# Dock.net
KiCad netlist of a schematic drawn in EAGLE
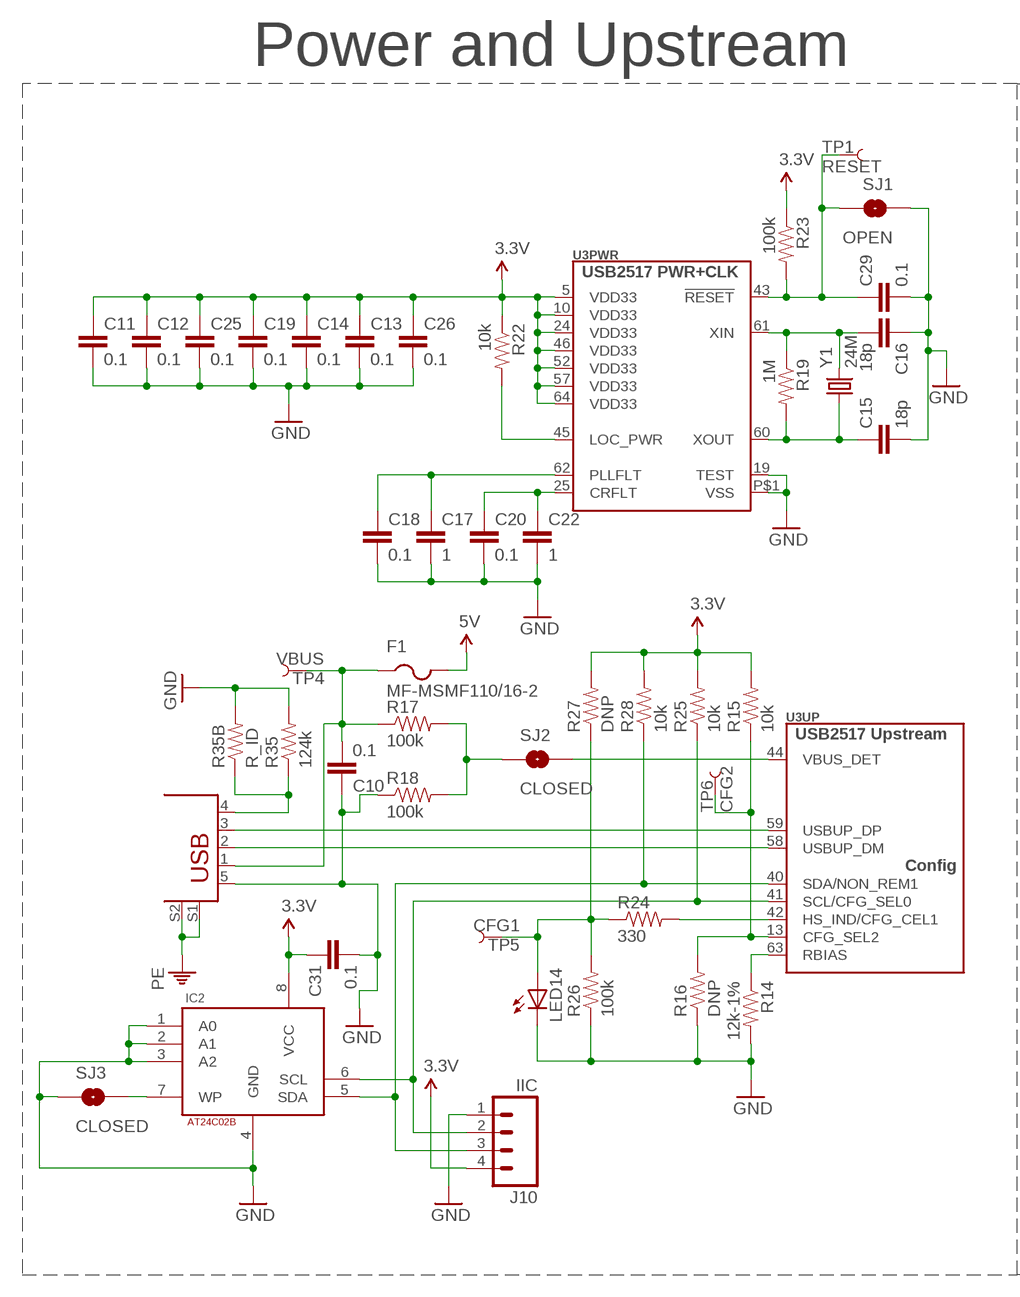
[diagram p0: schematic, sheet 1, part 1 of 2]
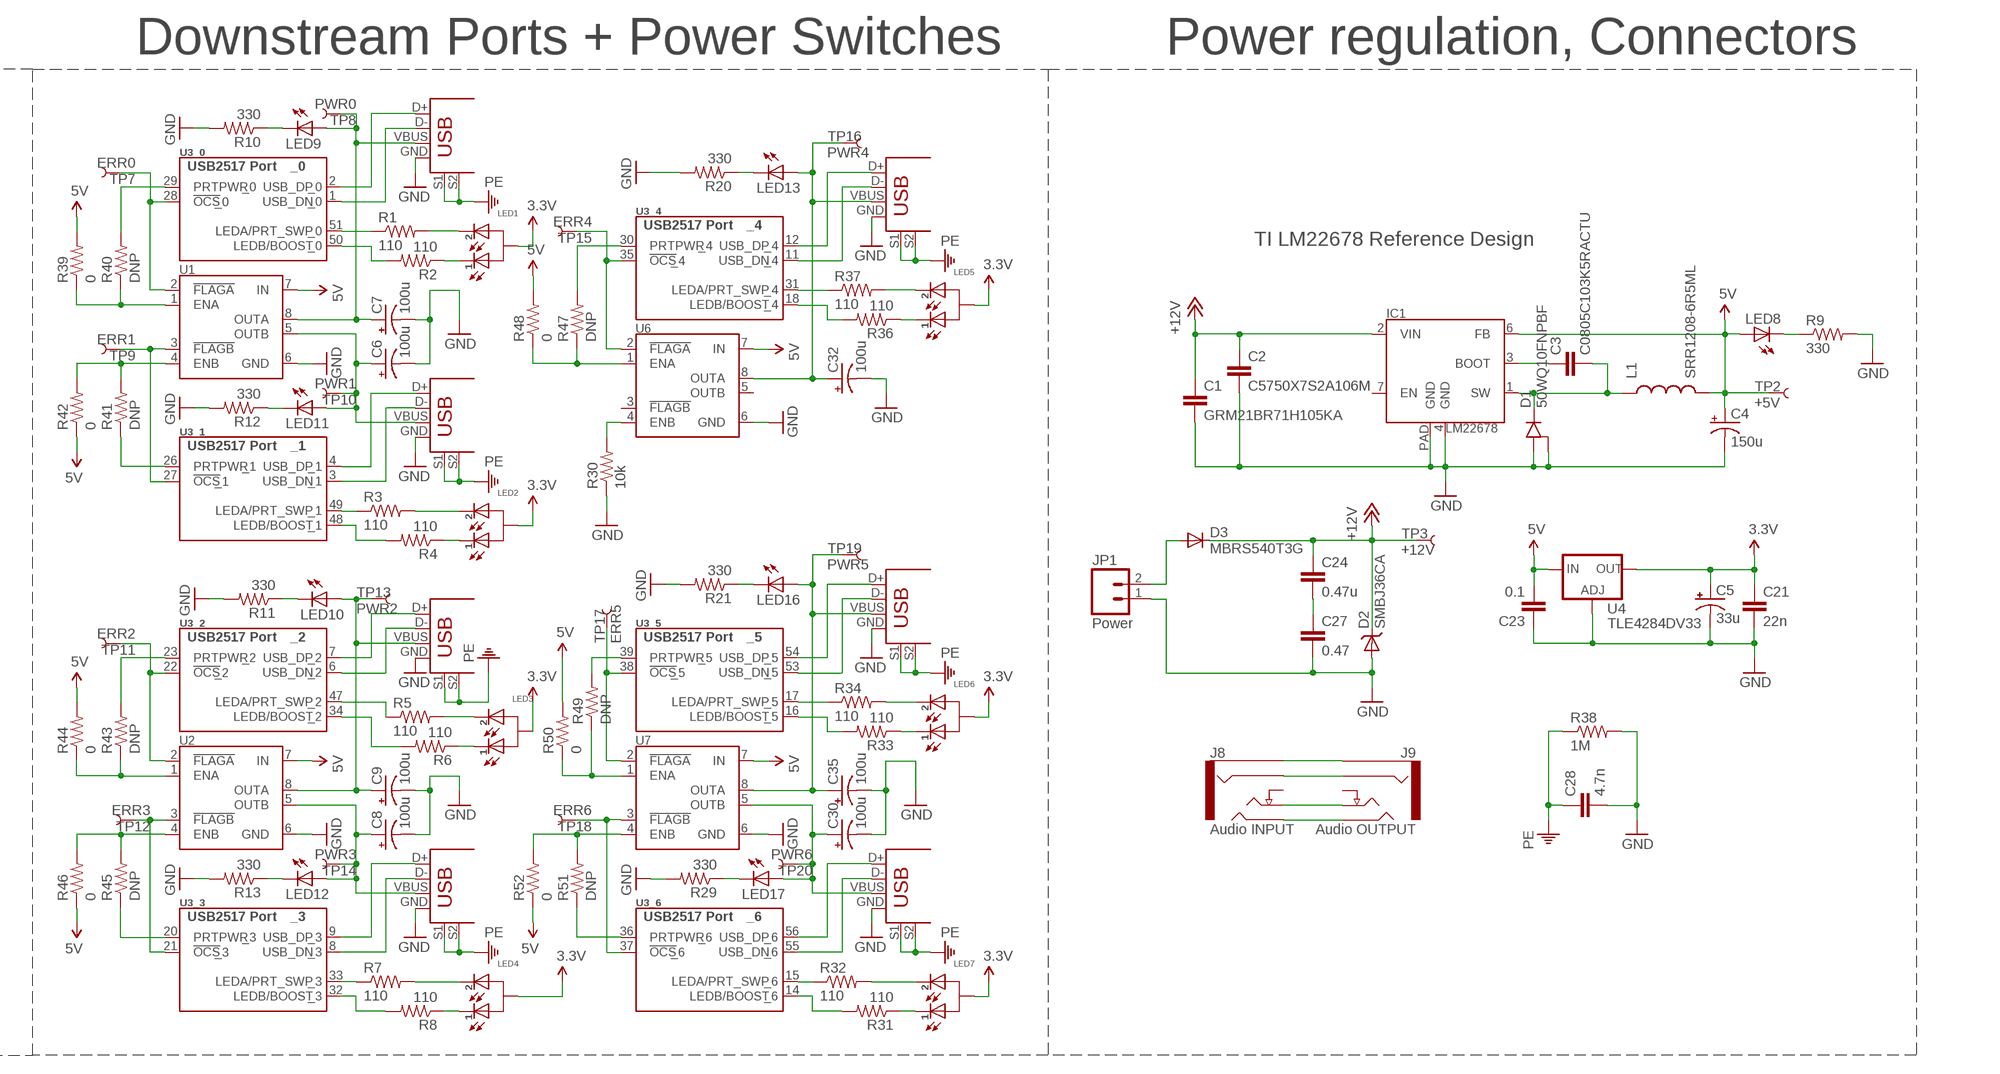
[diagram p1: schematic, sheet 1, part 2 of 2]

(export (version "E")
  (design (tool "Eeschema 10.0.6"))
  (components
    (comp (ref "C1")
      (value "GRM21BR71H105KA")
      (footprint "eagle-import:0805")
      (libsource (lib "eagle-import") (part "CAP0805"))
    )
    (comp (ref "C2")
      (value "C5750X7S2A106M")
      (footprint "eagle-import:2220")
      (libsource (lib "eagle-import") (part "CAP2220"))
    )
    (comp (ref "C3")
      (value "C0805C103K5RACTU")
      (footprint "eagle-import:0805")
      (libsource (lib "eagle-import") (part "CAP0805"))
    )
    (comp (ref "C4")
      (value "150u")
      (footprint "eagle-import:PANASONIC_D")
      (libsource (lib "eagle-import") (part "CAP_POLD"))
    )
    (comp (ref "C5")
      (value "33u")
      (footprint "eagle-import:PANASONIC_C")
      (libsource (lib "eagle-import") (part "CAP_POLC"))
    )
    (comp (ref "C6")
      (value "100u")
      (footprint "eagle-import:PANASONIC_D")
      (libsource (lib "eagle-import") (part "CAP_POLD"))
    )
    (comp (ref "C7")
      (value "100u")
      (footprint "eagle-import:PANASONIC_D")
      (libsource (lib "eagle-import") (part "CAP_POLD"))
    )
    (comp (ref "C8")
      (value "100u")
      (footprint "eagle-import:PANASONIC_D")
      (libsource (lib "eagle-import") (part "CAP_POLD"))
    )
    (comp (ref "C9")
      (value "100u")
      (footprint "eagle-import:PANASONIC_D")
      (libsource (lib "eagle-import") (part "CAP_POLD"))
    )
    (comp (ref "C10")
      (value "0.1")
      (footprint "eagle-import:0402-CAP")
      (libsource (lib "eagle-import") (part "CAP0402-CAP"))
    )
    (comp (ref "C11")
      (value "0.1")
      (footprint "eagle-import:0402-CAP")
      (libsource (lib "eagle-import") (part "CAP0402-CAP"))
    )
    (comp (ref "C12")
      (value "0.1")
      (footprint "eagle-import:0402-CAP")
      (libsource (lib "eagle-import") (part "CAP0402-CAP"))
    )
    (comp (ref "C13")
      (value "0.1")
      (footprint "eagle-import:0402-CAP")
      (libsource (lib "eagle-import") (part "CAP0402-CAP"))
    )
    (comp (ref "C14")
      (value "0.1")
      (footprint "eagle-import:0402-CAP")
      (libsource (lib "eagle-import") (part "CAP0402-CAP"))
    )
    (comp (ref "C15")
      (value "18p")
      (footprint "eagle-import:0402-CAP")
      (libsource (lib "eagle-import") (part "CAP0402-CAP"))
    )
    (comp (ref "C16")
      (value "18p")
      (footprint "eagle-import:0402-CAP")
      (libsource (lib "eagle-import") (part "CAP0402-CAP"))
    )
    (comp (ref "C17")
      (value "1")
      (footprint "eagle-import:0402-CAP")
      (libsource (lib "eagle-import") (part "CAP0402-CAP"))
    )
    (comp (ref "C18")
      (value "0.1")
      (footprint "eagle-import:0402-CAP")
      (libsource (lib "eagle-import") (part "CAP0402-CAP"))
    )
    (comp (ref "C19")
      (value "0.1")
      (footprint "eagle-import:0402-CAP")
      (libsource (lib "eagle-import") (part "CAP0402-CAP"))
    )
    (comp (ref "C20")
      (value "0.1")
      (footprint "eagle-import:0402-CAP")
      (libsource (lib "eagle-import") (part "CAP0402-CAP"))
    )
    (comp (ref "C21")
      (value "22n")
      (footprint "eagle-import:0402-CAP")
      (libsource (lib "eagle-import") (part "CAP0402-CAP"))
    )
    (comp (ref "C22")
      (value "1")
      (footprint "eagle-import:0402-CAP")
      (libsource (lib "eagle-import") (part "CAP0402-CAP"))
    )
    (comp (ref "C23")
      (value "0.1")
      (footprint "eagle-import:0402-CAP")
      (libsource (lib "eagle-import") (part "CAP0402-CAP"))
    )
    (comp (ref "C24")
      (value "0.47u")
      (footprint "eagle-import:0805")
      (libsource (lib "eagle-import") (part "CAP0805"))
    )
    (comp (ref "C25")
      (value "0.1")
      (footprint "eagle-import:0402-CAP")
      (libsource (lib "eagle-import") (part "CAP0402-CAP"))
    )
    (comp (ref "C26")
      (value "0.1")
      (footprint "eagle-import:0402-CAP")
      (libsource (lib "eagle-import") (part "CAP0402-CAP"))
    )
    (comp (ref "C27")
      (value "0.47")
      (footprint "eagle-import:0805")
      (libsource (lib "eagle-import") (part "CAP0805"))
    )
    (comp (ref "C28")
      (value "4.7n")
      (footprint "eagle-import:0805")
      (libsource (lib "eagle-import") (part "CAP0805"))
    )
    (comp (ref "C29")
      (value "0.1")
      (footprint "eagle-import:0402-CAP")
      (libsource (lib "eagle-import") (part "CAP0402-CAP"))
    )
    (comp (ref "C30")
      (value "100u")
      (footprint "eagle-import:PANASONIC_D")
      (libsource (lib "eagle-import") (part "CAP_POLD"))
    )
    (comp (ref "C31")
      (value "0.1")
      (footprint "eagle-import:0402-CAP")
      (libsource (lib "eagle-import") (part "CAP0402-CAP"))
    )
    (comp (ref "C32")
      (value "100u")
      (footprint "eagle-import:PANASONIC_D")
      (libsource (lib "eagle-import") (part "CAP_POLD"))
    )
    (comp (ref "C35")
      (value "100u")
      (footprint "eagle-import:PANASONIC_D")
      (libsource (lib "eagle-import") (part "CAP_POLD"))
    )
    (comp (ref "D1")
      (value "50WQ10FNPBF")
      (footprint "eagle-import:V-REG_DPACK")
      (libsource (lib "eagle-import") (part "DIODE_COMMON_CAT-DPAK"))
    )
    (comp (ref "D2")
      (value "SMBJ36CA")
      (footprint "eagle-import:SMB-DIODE")
      (libsource (lib "eagle-import") (part "DIODE-TVS-SMB"))
    )
    (comp (ref "D3")
      (value "MBRS540T3G")
      (footprint "eagle-import:SMC")
      (libsource (lib "eagle-import") (part "DIODESMC/DO-214AB"))
    )
    (comp (ref "F1")
      (value "MF-MSMF110/16-2")
      (footprint "eagle-import:1812")
      (libsource (lib "eagle-import") (part "PTCFUSE-1812"))
    )
    (comp (ref "IC1")
      (value "LM22678")
      (footprint "eagle-import:TO-263")
      (libsource (lib "eagle-import") (part "LM22678"))
    )
    (comp (ref "IC2")
      (value "ATMEL-AT24C02B-SS")
      (footprint "eagle-import:SOIC8")
      (libsource (lib "eagle-import") (part "ATMEL-AT24C02B-SS"))
    )
    (comp (ref "J0")
      (value "USB_MINIB_SHIELD-10118193")
      (footprint "eagle-import:10118193")
      (libsource (lib "eagle-import") (part "USB_MINIB_SHIELD-10118193"))
    )
    (comp (ref "J1")
      (value "USB-A-S-RA-VERT")
      (footprint "eagle-import:USB-A-TH-VERT")
      (libsource (lib "eagle-import") (part "USB-A-S-RA-VERT"))
    )
    (comp (ref "J2")
      (value "USB-A-S-RA-VERT")
      (footprint "eagle-import:USB-A-TH-VERT")
      (libsource (lib "eagle-import") (part "USB-A-S-RA-VERT"))
    )
    (comp (ref "J3")
      (value "USB-A-S-RA-VERT")
      (footprint "eagle-import:USB-A-TH-VERT")
      (libsource (lib "eagle-import") (part "USB-A-S-RA-VERT"))
    )
    (comp (ref "J4")
      (value "USB-A-S-RA-VERT")
      (footprint "eagle-import:USB-A-TH-VERT")
      (libsource (lib "eagle-import") (part "USB-A-S-RA-VERT"))
    )
    (comp (ref "J5")
      (value "USB-A-S-RA-VERT")
      (footprint "eagle-import:USB-A-TH-VERT")
      (libsource (lib "eagle-import") (part "USB-A-S-RA-VERT"))
    )
    (comp (ref "J6")
      (value "USB-A-S-RA-VERT")
      (footprint "eagle-import:USB-A-TH-VERT")
      (libsource (lib "eagle-import") (part "USB-A-S-RA-VERT"))
    )
    (comp (ref "J7")
      (value "USB-A-S-RA-VERT")
      (footprint "eagle-import:USB-A-TH-VERT")
      (libsource (lib "eagle-import") (part "USB-A-S-RA-VERT"))
    )
    (comp (ref "J8")
      (value "Audio INPUT")
      (footprint "eagle-import:SJ-4351X")
      (libsource (lib "eagle-import") (part "AUDIO-JACK-4PSWSJ-43515"))
    )
    (comp (ref "J9")
      (value "Audio OUTPUT")
      (footprint "eagle-import:SJ-4351X")
      (libsource (lib "eagle-import") (part "AUDIO-JACK-4PSWSJ-43515"))
    )
    (comp (ref "J10")
      (value "IIC")
      (footprint "eagle-import:1X04")
      (libsource (lib "eagle-import") (part "M04PTH"))
    )
    (comp (ref "JP1")
      (value "Power")
      (footprint "eagle-import:2-1445055-2")
      (libsource (lib "eagle-import") (part "M022-1445055-2"))
    )
    (comp (ref "L1")
      (value "SRR1208-6R5ML")
      (footprint "eagle-import:SRR1208")
      (libsource (lib "eagle-import") (part "INDUCTORSRR1208"))
    )
    (comp (ref "LED1")
      (value "LED_2X_COMMON_ANODE")
      (footprint "eagle-import:LED_DUAL_3MMX1MM")
      (libsource (lib "eagle-import") (part "LED_2X_COMMON_ANODE"))
    )
    (comp (ref "LED2")
      (value "LED_2X_COMMON_ANODE")
      (footprint "eagle-import:LED_DUAL_3MMX1MM")
      (libsource (lib "eagle-import") (part "LED_2X_COMMON_ANODE"))
    )
    (comp (ref "LED3")
      (value "LED_2X_COMMON_ANODE")
      (footprint "eagle-import:LED_DUAL_3MMX1MM")
      (libsource (lib "eagle-import") (part "LED_2X_COMMON_ANODE"))
    )
    (comp (ref "LED4")
      (value "LED_2X_COMMON_ANODE")
      (footprint "eagle-import:LED_DUAL_3MMX1MM")
      (libsource (lib "eagle-import") (part "LED_2X_COMMON_ANODE"))
    )
    (comp (ref "LED5")
      (value "LED_2X_COMMON_ANODE")
      (footprint "eagle-import:LED_DUAL_3MMX1MM")
      (libsource (lib "eagle-import") (part "LED_2X_COMMON_ANODE"))
    )
    (comp (ref "LED6")
      (value "LED_2X_COMMON_ANODE")
      (footprint "eagle-import:LED_DUAL_3MMX1MM")
      (libsource (lib "eagle-import") (part "LED_2X_COMMON_ANODE"))
    )
    (comp (ref "LED7")
      (value "LED_2X_COMMON_ANODE")
      (footprint "eagle-import:LED_DUAL_3MMX1MM")
      (libsource (lib "eagle-import") (part "LED_2X_COMMON_ANODE"))
    )
    (comp (ref "LED8")
      (value "LED0603")
      (footprint "eagle-import:LED-0603")
      (libsource (lib "eagle-import") (part "LED0603"))
    )
    (comp (ref "LED9")
      (value "LED0603")
      (footprint "eagle-import:LED-0603")
      (libsource (lib "eagle-import") (part "LED0603"))
    )
    (comp (ref "LED10")
      (value "LED0603")
      (footprint "eagle-import:LED-0603")
      (libsource (lib "eagle-import") (part "LED0603"))
    )
    (comp (ref "LED11")
      (value "LED0603")
      (footprint "eagle-import:LED-0603")
      (libsource (lib "eagle-import") (part "LED0603"))
    )
    (comp (ref "LED12")
      (value "LED0603")
      (footprint "eagle-import:LED-0603")
      (libsource (lib "eagle-import") (part "LED0603"))
    )
    (comp (ref "LED13")
      (value "LED0603")
      (footprint "eagle-import:LED-0603")
      (libsource (lib "eagle-import") (part "LED0603"))
    )
    (comp (ref "LED14")
      (value "LED0603")
      (footprint "eagle-import:LED-0603")
      (libsource (lib "eagle-import") (part "LED0603"))
    )
    (comp (ref "LED16")
      (value "LED0603")
      (footprint "eagle-import:LED-0603")
      (libsource (lib "eagle-import") (part "LED0603"))
    )
    (comp (ref "LED17")
      (value "LED0603")
      (footprint "eagle-import:LED-0603")
      (libsource (lib "eagle-import") (part "LED0603"))
    )
    (comp (ref "R1")
      (value "110")
      (footprint "eagle-import:0402-RES")
      (libsource (lib "eagle-import") (part "RESISTOR0402-RES"))
    )
    (comp (ref "R2")
      (value "110")
      (footprint "eagle-import:0402-RES")
      (libsource (lib "eagle-import") (part "RESISTOR0402-RES"))
    )
    (comp (ref "R3")
      (value "110")
      (footprint "eagle-import:0402-RES")
      (libsource (lib "eagle-import") (part "RESISTOR0402-RES"))
    )
    (comp (ref "R4")
      (value "110")
      (footprint "eagle-import:0402-RES")
      (libsource (lib "eagle-import") (part "RESISTOR0402-RES"))
    )
    (comp (ref "R5")
      (value "110")
      (footprint "eagle-import:0402-RES")
      (libsource (lib "eagle-import") (part "RESISTOR0402-RES"))
    )
    (comp (ref "R6")
      (value "110")
      (footprint "eagle-import:0402-RES")
      (libsource (lib "eagle-import") (part "RESISTOR0402-RES"))
    )
    (comp (ref "R7")
      (value "110")
      (footprint "eagle-import:0402-RES")
      (libsource (lib "eagle-import") (part "RESISTOR0402-RES"))
    )
    (comp (ref "R8")
      (value "110")
      (footprint "eagle-import:0402-RES")
      (libsource (lib "eagle-import") (part "RESISTOR0402-RES"))
    )
    (comp (ref "R9")
      (value "330")
      (footprint "eagle-import:0402-RES")
      (libsource (lib "eagle-import") (part "RESISTOR0402-RES"))
    )
    (comp (ref "R10")
      (value "330")
      (footprint "eagle-import:0402-RES")
      (libsource (lib "eagle-import") (part "RESISTOR0402-RES"))
    )
    (comp (ref "R11")
      (value "330")
      (footprint "eagle-import:0402-RES")
      (libsource (lib "eagle-import") (part "RESISTOR0402-RES"))
    )
    (comp (ref "R12")
      (value "330")
      (footprint "eagle-import:0402-RES")
      (libsource (lib "eagle-import") (part "RESISTOR0402-RES"))
    )
    (comp (ref "R13")
      (value "330")
      (footprint "eagle-import:0402-RES")
      (libsource (lib "eagle-import") (part "RESISTOR0402-RES"))
    )
    (comp (ref "R14")
      (value "12k-1%")
      (footprint "eagle-import:0402-RES")
      (libsource (lib "eagle-import") (part "RESISTOR0402-RES"))
    )
    (comp (ref "R15")
      (value "10k")
      (footprint "eagle-import:0402-RES")
      (libsource (lib "eagle-import") (part "RESISTOR0402-RES"))
    )
    (comp (ref "R16")
      (value "DNP")
      (footprint "eagle-import:0402-RES")
      (libsource (lib "eagle-import") (part "RESISTOR0402-RES"))
    )
    (comp (ref "R17")
      (value "100k")
      (footprint "eagle-import:0402-RES")
      (libsource (lib "eagle-import") (part "RESISTOR0402-RES"))
    )
    (comp (ref "R18")
      (value "100k")
      (footprint "eagle-import:0402-RES")
      (libsource (lib "eagle-import") (part "RESISTOR0402-RES"))
    )
    (comp (ref "R19")
      (value "1M")
      (footprint "eagle-import:0402-RES")
      (libsource (lib "eagle-import") (part "RESISTOR0402-RES"))
    )
    (comp (ref "R20")
      (value "330")
      (footprint "eagle-import:0402-RES")
      (libsource (lib "eagle-import") (part "RESISTOR0402-RES"))
    )
    (comp (ref "R21")
      (value "330")
      (footprint "eagle-import:0402-RES")
      (libsource (lib "eagle-import") (part "RESISTOR0402-RES"))
    )
    (comp (ref "R22")
      (value "10k")
      (footprint "eagle-import:0402-RES")
      (libsource (lib "eagle-import") (part "RESISTOR0402-RES"))
    )
    (comp (ref "R23")
      (value "100k")
      (footprint "eagle-import:0402-RES")
      (libsource (lib "eagle-import") (part "RESISTOR0402-RES"))
    )
    (comp (ref "R24")
      (value "330")
      (footprint "eagle-import:0402-RES")
      (libsource (lib "eagle-import") (part "RESISTOR0402-RES"))
    )
    (comp (ref "R25")
      (value "10k")
      (footprint "eagle-import:0402-RES")
      (libsource (lib "eagle-import") (part "RESISTOR0402-RES"))
    )
    (comp (ref "R26")
      (value "100k")
      (footprint "eagle-import:0402-RES")
      (libsource (lib "eagle-import") (part "RESISTOR0402-RES"))
    )
    (comp (ref "R27")
      (value "DNP")
      (footprint "eagle-import:0402-RES")
      (libsource (lib "eagle-import") (part "RESISTOR0402-RES"))
    )
    (comp (ref "R28")
      (value "10k")
      (footprint "eagle-import:0402-RES")
      (libsource (lib "eagle-import") (part "RESISTOR0402-RES"))
    )
    (comp (ref "R29")
      (value "330")
      (footprint "eagle-import:0402-RES")
      (libsource (lib "eagle-import") (part "RESISTOR0402-RES"))
    )
    (comp (ref "R30")
      (value "10k")
      (footprint "eagle-import:0402-RES")
      (libsource (lib "eagle-import") (part "RESISTOR0402-RES"))
    )
    (comp (ref "R31")
      (value "110")
      (footprint "eagle-import:0402-RES")
      (libsource (lib "eagle-import") (part "RESISTOR0402-RES"))
    )
    (comp (ref "R32")
      (value "110")
      (footprint "eagle-import:0402-RES")
      (libsource (lib "eagle-import") (part "RESISTOR0402-RES"))
    )
    (comp (ref "R33")
      (value "110")
      (footprint "eagle-import:0402-RES")
      (libsource (lib "eagle-import") (part "RESISTOR0402-RES"))
    )
    (comp (ref "R34")
      (value "110")
      (footprint "eagle-import:0402-RES")
      (libsource (lib "eagle-import") (part "RESISTOR0402-RES"))
    )
    (comp (ref "R35")
      (value "124k")
      (footprint "eagle-import:0402-RES")
      (libsource (lib "eagle-import") (part "RESISTOR0402-RES"))
    )
    (comp (ref "R35B")
      (value "R_ID")
      (footprint "eagle-import:AXIAL-0.4")
      (libsource (lib "eagle-import") (part "RESISTORPTH-1/4W"))
    )
    (comp (ref "R36")
      (value "110")
      (footprint "eagle-import:0402-RES")
      (libsource (lib "eagle-import") (part "RESISTOR0402-RES"))
    )
    (comp (ref "R37")
      (value "110")
      (footprint "eagle-import:0402-RES")
      (libsource (lib "eagle-import") (part "RESISTOR0402-RES"))
    )
    (comp (ref "R38")
      (value "1M")
      (footprint "eagle-import:0805")
      (libsource (lib "eagle-import") (part "RESISTOR0805-RES"))
    )
    (comp (ref "R39")
      (value "0")
      (footprint "eagle-import:0402-RES")
      (libsource (lib "eagle-import") (part "RESISTOR0402-RES"))
    )
    (comp (ref "R40")
      (value "DNP")
      (footprint "eagle-import:0402-RES")
      (libsource (lib "eagle-import") (part "RESISTOR0402-RES"))
    )
    (comp (ref "R41")
      (value "DNP")
      (footprint "eagle-import:0402-RES")
      (libsource (lib "eagle-import") (part "RESISTOR0402-RES"))
    )
    (comp (ref "R42")
      (value "0")
      (footprint "eagle-import:0402-RES")
      (libsource (lib "eagle-import") (part "RESISTOR0402-RES"))
    )
    (comp (ref "R43")
      (value "DNP")
      (footprint "eagle-import:0402-RES")
      (libsource (lib "eagle-import") (part "RESISTOR0402-RES"))
    )
    (comp (ref "R44")
      (value "0")
      (footprint "eagle-import:0402-RES")
      (libsource (lib "eagle-import") (part "RESISTOR0402-RES"))
    )
    (comp (ref "R45")
      (value "DNP")
      (footprint "eagle-import:0402-RES")
      (libsource (lib "eagle-import") (part "RESISTOR0402-RES"))
    )
    (comp (ref "R46")
      (value "0")
      (footprint "eagle-import:0402-RES")
      (libsource (lib "eagle-import") (part "RESISTOR0402-RES"))
    )
    (comp (ref "R47")
      (value "DNP")
      (footprint "eagle-import:0402-RES")
      (libsource (lib "eagle-import") (part "RESISTOR0402-RES"))
    )
    (comp (ref "R48")
      (value "0")
      (footprint "eagle-import:0402-RES")
      (libsource (lib "eagle-import") (part "RESISTOR0402-RES"))
    )
    (comp (ref "R49")
      (value "DNP")
      (footprint "eagle-import:0402-RES")
      (libsource (lib "eagle-import") (part "RESISTOR0402-RES"))
    )
    (comp (ref "R50")
      (value "0")
      (footprint "eagle-import:0402-RES")
      (libsource (lib "eagle-import") (part "RESISTOR0402-RES"))
    )
    (comp (ref "R51")
      (value "DNP")
      (footprint "eagle-import:0402-RES")
      (libsource (lib "eagle-import") (part "RESISTOR0402-RES"))
    )
    (comp (ref "R52")
      (value "0")
      (footprint "eagle-import:0402-RES")
      (libsource (lib "eagle-import") (part "RESISTOR0402-RES"))
    )
    (comp (ref "SJ1")
      (value "OPEN")
      (footprint "eagle-import:SJ_2S-NO")
      (libsource (lib "eagle-import") (part "SOLDERJUMPERNO"))
    )
    (comp (ref "SJ2")
      (value "CLOSED")
      (footprint "eagle-import:SJ_2S-TRACE")
      (libsource (lib "eagle-import") (part "SOLDERJUMPERTRACE"))
    )
    (comp (ref "SJ3")
      (value "CLOSED")
      (footprint "eagle-import:SJ_2S-TRACE")
      (libsource (lib "eagle-import") (part "SOLDERJUMPERTRACE"))
    )
    (comp (ref "TP1")
      (value "RESET")
      (footprint "eagle-import:PAD.03X.03")
      (libsource (lib "eagle-import") (part "TEST-POINT3"))
    )
    (comp (ref "TP2")
      (value "+5V")
      (footprint "eagle-import:PAD.03X.03")
      (libsource (lib "eagle-import") (part "TEST-POINT3"))
    )
    (comp (ref "TP3")
      (value "+12V")
      (footprint "eagle-import:PAD.03X.03")
      (libsource (lib "eagle-import") (part "TEST-POINT3"))
    )
    (comp (ref "TP4")
      (value "VBUS")
      (footprint "eagle-import:PAD.03X.03")
      (libsource (lib "eagle-import") (part "TEST-POINT3"))
    )
    (comp (ref "TP5")
      (value "CFG1")
      (footprint "eagle-import:PAD.03X.03")
      (libsource (lib "eagle-import") (part "TEST-POINT3"))
    )
    (comp (ref "TP6")
      (value "CFG2")
      (footprint "eagle-import:PAD.03X.03")
      (libsource (lib "eagle-import") (part "TEST-POINT3"))
    )
    (comp (ref "TP7")
      (value "ERR0")
      (footprint "eagle-import:PAD.03X.03")
      (libsource (lib "eagle-import") (part "TEST-POINT3"))
    )
    (comp (ref "TP8")
      (value "PWR0")
      (footprint "eagle-import:PAD.03X.03")
      (libsource (lib "eagle-import") (part "TEST-POINT3"))
    )
    (comp (ref "TP9")
      (value "ERR1")
      (footprint "eagle-import:PAD.03X.03")
      (libsource (lib "eagle-import") (part "TEST-POINT3"))
    )
    (comp (ref "TP10")
      (value "PWR1")
      (footprint "eagle-import:PAD.03X.03")
      (libsource (lib "eagle-import") (part "TEST-POINT3"))
    )
    (comp (ref "TP11")
      (value "ERR2")
      (footprint "eagle-import:PAD.03X.03")
      (libsource (lib "eagle-import") (part "TEST-POINT3"))
    )
    (comp (ref "TP12")
      (value "ERR3")
      (footprint "eagle-import:PAD.03X.03")
      (libsource (lib "eagle-import") (part "TEST-POINT3"))
    )
    (comp (ref "TP13")
      (value "PWR2")
      (footprint "eagle-import:PAD.03X.03")
      (libsource (lib "eagle-import") (part "TEST-POINT3"))
    )
    (comp (ref "TP14")
      (value "PWR3")
      (footprint "eagle-import:PAD.03X.03")
      (libsource (lib "eagle-import") (part "TEST-POINT3"))
    )
    (comp (ref "TP15")
      (value "ERR4")
      (footprint "eagle-import:PAD.03X.03")
      (libsource (lib "eagle-import") (part "TEST-POINT3"))
    )
    (comp (ref "TP16")
      (value "PWR4")
      (footprint "eagle-import:PAD.03X.03")
      (libsource (lib "eagle-import") (part "TEST-POINT3"))
    )
    (comp (ref "TP17")
      (value "ERR5")
      (footprint "eagle-import:PAD.03X.03")
      (libsource (lib "eagle-import") (part "TEST-POINT3"))
    )
    (comp (ref "TP18")
      (value "ERR6")
      (footprint "eagle-import:PAD.03X.03")
      (libsource (lib "eagle-import") (part "TEST-POINT3"))
    )
    (comp (ref "TP19")
      (value "PWR5")
      (footprint "eagle-import:PAD.03X.03")
      (libsource (lib "eagle-import") (part "TEST-POINT3"))
    )
    (comp (ref "TP20")
      (value "PWR6")
      (footprint "eagle-import:PAD.03X.03")
      (libsource (lib "eagle-import") (part "TEST-POINT3"))
    )
    (comp (ref "U1")
      (value "MIC2026")
      (footprint "eagle-import:SOIC8")
      (libsource (lib "eagle-import") (part "MIC2026"))
    )
    (comp (ref "U2")
      (value "MIC2026")
      (footprint "eagle-import:SOIC8")
      (libsource (lib "eagle-import") (part "MIC2026"))
    )
    (comp (ref "U3")
      (value "USB2517")
      (footprint "eagle-import:QFN-64-PAD")
      (libsource (lib "eagle-import") (part "USB2517"))
    )
    (comp (ref "U4")
      (value "TLE4284DV33")
      (footprint "eagle-import:V-REG_DPACK")
      (libsource (lib "eagle-import") (part "V_REG_317DPACK"))
    )
    (comp (ref "U6")
      (value "MIC2026")
      (footprint "eagle-import:SOIC8")
      (libsource (lib "eagle-import") (part "MIC2026"))
    )
    (comp (ref "U7")
      (value "MIC2026")
      (footprint "eagle-import:SOIC8")
      (libsource (lib "eagle-import") (part "MIC2026"))
    )
    (comp (ref "Y1")
      (value "24M")
      (footprint "eagle-import:HC49USX")
      (libsource (lib "eagle-import") (part "CRYSTAL"))
    )
  )
  (nets
    (net (code "1") (name "+12V") (class "Default")
      (node (ref "C1") (pin "1") (pinfunction "1_1") (pintype "passive"))
      (node (ref "C2") (pin "1") (pinfunction "1_1") (pintype "passive"))
      (node (ref "C24") (pin "1") (pinfunction "1_1") (pintype "passive"))
      (node (ref "D2") (pin "C") (pinfunction "C_C") (pintype "passive"))
      (node (ref "D3") (pin "C") (pinfunction "C_C") (pintype "passive"))
      (node (ref "IC1") (pin "2") (pinfunction "VIN_2") (pintype "bidirectional"))
      (node (ref "TP3") (pin "P$1") (pinfunction "1_P$1") (pintype "bidirectional"))
    )
    (net (code "2") (name "3.3V") (class "Default")
      (node (ref "C11") (pin "1") (pinfunction "1_1") (pintype "passive"))
      (node (ref "C12") (pin "1") (pinfunction "1_1") (pintype "passive"))
      (node (ref "C13") (pin "1") (pinfunction "1_1") (pintype "passive"))
      (node (ref "C14") (pin "1") (pinfunction "1_1") (pintype "passive"))
      (node (ref "C19") (pin "1") (pinfunction "1_1") (pintype "passive"))
      (node (ref "C21") (pin "1") (pinfunction "1_1") (pintype "passive"))
      (node (ref "C25") (pin "1") (pinfunction "1_1") (pintype "passive"))
      (node (ref "C26") (pin "1") (pinfunction "1_1") (pintype "passive"))
      (node (ref "C31") (pin "1") (pinfunction "1_1") (pintype "passive"))
      (node (ref "C5") (pin "+") (pinfunction "+_+") (pintype "passive"))
      (node (ref "IC2") (pin "8") (pinfunction "VCC_8") (pintype "bidirectional"))
      (node (ref "J10") (pin "4") (pinfunction "4_4") (pintype "passive"))
      (node (ref "LED1") (pin "1") (pinfunction "A_1") (pintype "bidirectional"))
      (node (ref "LED2") (pin "1") (pinfunction "A_1") (pintype "bidirectional"))
      (node (ref "LED3") (pin "1") (pinfunction "A_1") (pintype "bidirectional"))
      (node (ref "LED4") (pin "1") (pinfunction "A_1") (pintype "bidirectional"))
      (node (ref "LED5") (pin "1") (pinfunction "A_1") (pintype "bidirectional"))
      (node (ref "LED6") (pin "1") (pinfunction "A_1") (pintype "bidirectional"))
      (node (ref "LED7") (pin "1") (pinfunction "A_1") (pintype "bidirectional"))
      (node (ref "R15") (pin "2") (pinfunction "2_2") (pintype "passive"))
      (node (ref "R22") (pin "1") (pinfunction "1_1") (pintype "passive"))
      (node (ref "R23") (pin "1") (pinfunction "1_1") (pintype "passive"))
      (node (ref "R25") (pin "2") (pinfunction "2_2") (pintype "passive"))
      (node (ref "R27") (pin "2") (pinfunction "2_2") (pintype "passive"))
      (node (ref "R28") (pin "2") (pinfunction "2_2") (pintype "passive"))
      (node (ref "U3") (pin "10") (pinfunction "VDD33_10") (pintype "bidirectional"))
      (node (ref "U3") (pin "24") (pinfunction "VDD33_24") (pintype "bidirectional"))
      (node (ref "U3") (pin "46") (pinfunction "VDD33_46") (pintype "bidirectional"))
      (node (ref "U3") (pin "5") (pinfunction "VDD33_5") (pintype "bidirectional"))
      (node (ref "U3") (pin "52") (pinfunction "VDD33_52") (pintype "bidirectional"))
      (node (ref "U3") (pin "57") (pinfunction "VDD33_57") (pintype "bidirectional"))
      (node (ref "U3") (pin "64") (pinfunction "VDD33_64") (pintype "bidirectional"))
      (node (ref "U4") (pin "4") (pinfunction "OUT_4") (pintype "output"))
    )
    (net (code "3") (name "5V") (class "Default")
      (node (ref "C23") (pin "2") (pinfunction "2_2") (pintype "passive"))
      (node (ref "C4") (pin "+") (pinfunction "+_+") (pintype "passive"))
      (node (ref "F1") (pin "2") (pinfunction "2_2") (pintype "passive"))
      (node (ref "IC1") (pin "6") (pinfunction "FB_6") (pintype "bidirectional"))
      (node (ref "L1") (pin "2") (pinfunction "2_2") (pintype "passive"))
      (node (ref "LED8") (pin "A") (pinfunction "A_A") (pintype "passive"))
      (node (ref "R39") (pin "2") (pinfunction "2_2") (pintype "passive"))
      (node (ref "R42") (pin "1") (pinfunction "1_1") (pintype "passive"))
      (node (ref "R44") (pin "2") (pinfunction "2_2") (pintype "passive"))
      (node (ref "R46") (pin "1") (pinfunction "1_1") (pintype "passive"))
      (node (ref "R48") (pin "2") (pinfunction "2_2") (pintype "passive"))
      (node (ref "R50") (pin "2") (pinfunction "2_2") (pintype "passive"))
      (node (ref "R52") (pin "1") (pinfunction "1_1") (pintype "passive"))
      (node (ref "TP2") (pin "P$1") (pinfunction "1_P$1") (pintype "bidirectional"))
      (node (ref "U1") (pin "7") (pinfunction "IN_7") (pintype "bidirectional"))
      (node (ref "U2") (pin "7") (pinfunction "IN_7") (pintype "bidirectional"))
      (node (ref "U4") (pin "3") (pinfunction "IN_3") (pintype "input"))
      (node (ref "U6") (pin "7") (pinfunction "IN_7") (pintype "bidirectional"))
      (node (ref "U7") (pin "7") (pinfunction "IN_7") (pintype "bidirectional"))
    )
    (net (code "4") (name "GND") (class "Default")
      (node (ref "C1") (pin "2") (pinfunction "2_2") (pintype "passive"))
      (node (ref "C10") (pin "1") (pinfunction "1_1") (pintype "passive"))
      (node (ref "C11") (pin "2") (pinfunction "2_2") (pintype "passive"))
      (node (ref "C12") (pin "2") (pinfunction "2_2") (pintype "passive"))
      (node (ref "C13") (pin "2") (pinfunction "2_2") (pintype "passive"))
      (node (ref "C14") (pin "2") (pinfunction "2_2") (pintype "passive"))
      (node (ref "C15") (pin "2") (pinfunction "2_2") (pintype "passive"))
      (node (ref "C16") (pin "1") (pinfunction "1_1") (pintype "passive"))
      (node (ref "C17") (pin "2") (pinfunction "2_2") (pintype "passive"))
      (node (ref "C18") (pin "2") (pinfunction "2_2") (pintype "passive"))
      (node (ref "C19") (pin "2") (pinfunction "2_2") (pintype "passive"))
      (node (ref "C2") (pin "2") (pinfunction "2_2") (pintype "passive"))
      (node (ref "C20") (pin "2") (pinfunction "2_2") (pintype "passive"))
      (node (ref "C21") (pin "2") (pinfunction "2_2") (pintype "passive"))
      (node (ref "C22") (pin "2") (pinfunction "2_2") (pintype "passive"))
      (node (ref "C23") (pin "1") (pinfunction "1_1") (pintype "passive"))
      (node (ref "C25") (pin "2") (pinfunction "2_2") (pintype "passive"))
      (node (ref "C26") (pin "2") (pinfunction "2_2") (pintype "passive"))
      (node (ref "C27") (pin "2") (pinfunction "2_2") (pintype "passive"))
      (node (ref "C28") (pin "2") (pinfunction "2_2") (pintype "passive"))
      (node (ref "C29") (pin "2") (pinfunction "2_2") (pintype "passive"))
      (node (ref "C30") (pin "-") (pinfunction "-_-") (pintype "passive"))
      (node (ref "C31") (pin "2") (pinfunction "2_2") (pintype "passive"))
      (node (ref "C32") (pin "-") (pinfunction "-_-") (pintype "passive"))
      (node (ref "C35") (pin "-") (pinfunction "-_-") (pintype "passive"))
      (node (ref "C4") (pin "-") (pinfunction "-_-") (pintype "passive"))
      (node (ref "C5") (pin "-") (pinfunction "-_-") (pintype "passive"))
      (node (ref "C6") (pin "-") (pinfunction "-_-") (pintype "passive"))
      (node (ref "C7") (pin "-") (pinfunction "-_-") (pintype "passive"))
      (node (ref "C8") (pin "-") (pinfunction "-_-") (pintype "passive"))
      (node (ref "C9") (pin "-") (pinfunction "-_-") (pintype "passive"))
      (node (ref "D1") (pin "1") (pinfunction "A_1") (pintype "passive"))
      (node (ref "D1") (pin "3") (pinfunction "A_3") (pintype "passive"))
      (node (ref "D2") (pin "A") (pinfunction "A_A") (pintype "passive"))
      (node (ref "IC1") (pin "4") (pinfunction "GND_4") (pintype "bidirectional"))
      (node (ref "IC1") (pin "PAD") (pinfunction "GND_PAD") (pintype "bidirectional"))
      (node (ref "IC2") (pin "1") (pinfunction "A0_1") (pintype "bidirectional"))
      (node (ref "IC2") (pin "2") (pinfunction "A1_2") (pintype "bidirectional"))
      (node (ref "IC2") (pin "3") (pinfunction "A2_3") (pintype "bidirectional"))
      (node (ref "IC2") (pin "4") (pinfunction "GND_4") (pintype "bidirectional"))
      (node (ref "J0") (pin "5") (pinfunction "GND_5") (pintype "bidirectional"))
      (node (ref "J1") (pin "GND") (pinfunction "GND_GND") (pintype "bidirectional"))
      (node (ref "J10") (pin "1") (pinfunction "1_1") (pintype "passive"))
      (node (ref "J2") (pin "GND") (pinfunction "GND_GND") (pintype "bidirectional"))
      (node (ref "J3") (pin "GND") (pinfunction "GND_GND") (pintype "bidirectional"))
      (node (ref "J4") (pin "GND") (pinfunction "GND_GND") (pintype "bidirectional"))
      (node (ref "J5") (pin "GND") (pinfunction "GND_GND") (pintype "bidirectional"))
      (node (ref "J6") (pin "GND") (pinfunction "GND_GND") (pintype "bidirectional"))
      (node (ref "J7") (pin "GND") (pinfunction "GND_GND") (pintype "bidirectional"))
      (node (ref "JP1") (pin "1") (pinfunction "1_1") (pintype "passive"))
      (node (ref "LED14") (pin "C") (pinfunction "C_C") (pintype "passive"))
      (node (ref "R10") (pin "2") (pinfunction "2_2") (pintype "passive"))
      (node (ref "R11") (pin "2") (pinfunction "2_2") (pintype "passive"))
      (node (ref "R12") (pin "2") (pinfunction "2_2") (pintype "passive"))
      (node (ref "R13") (pin "2") (pinfunction "2_2") (pintype "passive"))
      (node (ref "R14") (pin "2") (pinfunction "2_2") (pintype "passive"))
      (node (ref "R16") (pin "1") (pinfunction "1_1") (pintype "passive"))
      (node (ref "R18") (pin "1") (pinfunction "1_1") (pintype "passive"))
      (node (ref "R20") (pin "2") (pinfunction "2_2") (pintype "passive"))
      (node (ref "R21") (pin "2") (pinfunction "2_2") (pintype "passive"))
      (node (ref "R26") (pin "1") (pinfunction "1_1") (pintype "passive"))
      (node (ref "R29") (pin "2") (pinfunction "2_2") (pintype "passive"))
      (node (ref "R30") (pin "1") (pinfunction "1_1") (pintype "passive"))
      (node (ref "R35") (pin "2") (pinfunction "2_2") (pintype "passive"))
      (node (ref "R35B") (pin "P$2") (pinfunction "2_P$2") (pintype "passive"))
      (node (ref "R38") (pin "2") (pinfunction "2_2") (pintype "passive"))
      (node (ref "R9") (pin "2") (pinfunction "2_2") (pintype "passive"))
      (node (ref "SJ1") (pin "1") (pinfunction "1_1") (pintype "passive"))
      (node (ref "SJ3") (pin "1") (pinfunction "1_1") (pintype "passive"))
      (node (ref "U1") (pin "6") (pinfunction "GND_6") (pintype "bidirectional"))
      (node (ref "U2") (pin "6") (pinfunction "GND_6") (pintype "bidirectional"))
      (node (ref "U3") (pin "19") (pinfunction "TEST_19") (pintype "bidirectional"))
      (node (ref "U3") (pin "P$1") (pinfunction "VSS_P$1") (pintype "bidirectional"))
      (node (ref "U4") (pin "1") (pinfunction "ADJ_1") (pintype "input"))
      (node (ref "U6") (pin "6") (pinfunction "GND_6") (pintype "bidirectional"))
      (node (ref "U7") (pin "6") (pinfunction "GND_6") (pintype "bidirectional"))
    )
    (net (code "5") (name "Net-(C24-Pad2)") (class "Default")
      (node (ref "C24") (pin "2") (pinfunction "2_2") (pintype "passive"))
      (node (ref "C27") (pin "1") (pinfunction "1_1") (pintype "passive"))
    )
    (net (code "6") (name "Net-(D1-C)") (class "Default")
      (node (ref "C3") (pin "2") (pinfunction "2_2") (pintype "passive"))
      (node (ref "D1") (pin "4") (pinfunction "C_4") (pintype "passive"))
      (node (ref "IC1") (pin "1") (pinfunction "SW_1") (pintype "bidirectional"))
      (node (ref "L1") (pin "1") (pinfunction "1_1") (pintype "passive"))
    )
    (net (code "7") (name "Net-(D3-PadA)") (class "Default")
      (node (ref "D3") (pin "A") (pinfunction "A_A") (pintype "passive"))
      (node (ref "JP1") (pin "2") (pinfunction "2_2") (pintype "passive"))
    )
    (net (code "8") (name "Net-(IC1-BOOT)") (class "Default")
      (node (ref "C3") (pin "1") (pinfunction "1_1") (pintype "passive"))
      (node (ref "IC1") (pin "3") (pinfunction "BOOT_3") (pintype "bidirectional"))
    )
    (net (code "9") (name "Net-(IC2-SCL)") (class "Default")
      (node (ref "IC2") (pin "6") (pinfunction "SCL_6") (pintype "bidirectional"))
      (node (ref "J10") (pin "2") (pinfunction "2_2") (pintype "passive"))
      (node (ref "R25") (pin "1") (pinfunction "1_1") (pintype "passive"))
      (node (ref "U3") (pin "41") (pinfunction "SCL/CFG_SEL0_41") (pintype "bidirectional"))
    )
    (net (code "10") (name "Net-(IC2-SDA)") (class "Default")
      (node (ref "IC2") (pin "5") (pinfunction "SDA_5") (pintype "bidirectional"))
      (node (ref "J10") (pin "3") (pinfunction "3_3") (pintype "passive"))
      (node (ref "R28") (pin "1") (pinfunction "1_1") (pintype "passive"))
      (node (ref "U3") (pin "40") (pinfunction "SDA/NON_REM1_40") (pintype "bidirectional"))
    )
    (net (code "11") (name "Net-(IC2-WP)") (class "Default")
      (node (ref "IC2") (pin "7") (pinfunction "WP_7") (pintype "bidirectional"))
      (node (ref "SJ3") (pin "2") (pinfunction "2_2") (pintype "passive"))
    )
    (net (code "12") (name "Net-(J0-D+)") (class "Default")
      (node (ref "J0") (pin "3") (pinfunction "D+_3") (pintype "bidirectional"))
      (node (ref "U3") (pin "59") (pinfunction "USBUP_DP_59") (pintype "bidirectional"))
    )
    (net (code "13") (name "Net-(J0-D-)") (class "Default")
      (node (ref "J0") (pin "2") (pinfunction "D-_2") (pintype "bidirectional"))
      (node (ref "U3") (pin "58") (pinfunction "USBUP_DM_58") (pintype "bidirectional"))
    )
    (net (code "14") (name "Net-(J0-ID)") (class "Default")
      (node (ref "J0") (pin "4") (pinfunction "ID_4") (pintype "bidirectional"))
      (node (ref "R35") (pin "1") (pinfunction "1_1") (pintype "passive"))
      (node (ref "R35B") (pin "P$1") (pinfunction "1_P$1") (pintype "passive"))
    )
    (net (code "15") (name "Net-(J0-VBUS)") (class "Default")
      (node (ref "C10") (pin "2") (pinfunction "2_2") (pintype "passive"))
      (node (ref "F1") (pin "1") (pinfunction "1_1") (pintype "passive"))
      (node (ref "J0") (pin "1") (pinfunction "VBUS_1") (pintype "bidirectional"))
      (node (ref "R17") (pin "1") (pinfunction "1_1") (pintype "passive"))
      (node (ref "TP4") (pin "P$1") (pinfunction "1_P$1") (pintype "bidirectional"))
    )
    (net (code "16") (name "Net-(J8-RING1)") (class "Default")
      (node (ref "J8") (pin "3") (pinfunction "RING1_3") (pintype "bidirectional"))
      (node (ref "J9") (pin "3") (pinfunction "RING1_3") (pintype "bidirectional"))
    )
    (net (code "17") (name "Net-(J8-RING2)") (class "Default")
      (node (ref "J8") (pin "4") (pinfunction "RING2_4") (pintype "bidirectional"))
      (node (ref "J9") (pin "4") (pinfunction "RING2_4") (pintype "bidirectional"))
    )
    (net (code "18") (name "Net-(J8-SLEEVE)") (class "Default")
      (node (ref "J8") (pin "1") (pinfunction "SLEEVE_1") (pintype "bidirectional"))
      (node (ref "J9") (pin "1") (pinfunction "SLEEVE_1") (pintype "bidirectional"))
    )
    (net (code "19") (name "Net-(J8-TIP)") (class "Default")
      (node (ref "J8") (pin "2") (pinfunction "TIP_2") (pintype "bidirectional"))
      (node (ref "J9") (pin "2") (pinfunction "TIP_2") (pintype "bidirectional"))
    )
    (net (code "20") (name "Net-(LED1-C1)") (class "Default")
      (node (ref "LED1") (pin "2") (pinfunction "C1_2") (pintype "bidirectional"))
      (node (ref "R2") (pin "1") (pinfunction "1_1") (pintype "passive"))
    )
    (net (code "21") (name "Net-(LED1-C2)") (class "Default")
      (node (ref "LED1") (pin "3") (pinfunction "C2_3") (pintype "bidirectional"))
      (node (ref "R1") (pin "2") (pinfunction "2_2") (pintype "passive"))
    )
    (net (code "22") (name "Net-(LED2-C1)") (class "Default")
      (node (ref "LED2") (pin "2") (pinfunction "C1_2") (pintype "bidirectional"))
      (node (ref "R4") (pin "1") (pinfunction "1_1") (pintype "passive"))
    )
    (net (code "23") (name "Net-(LED2-C2)") (class "Default")
      (node (ref "LED2") (pin "3") (pinfunction "C2_3") (pintype "bidirectional"))
      (node (ref "R3") (pin "2") (pinfunction "2_2") (pintype "passive"))
    )
    (net (code "24") (name "Net-(LED3-C1)") (class "Default")
      (node (ref "LED3") (pin "2") (pinfunction "C1_2") (pintype "bidirectional"))
      (node (ref "R6") (pin "1") (pinfunction "1_1") (pintype "passive"))
    )
    (net (code "25") (name "Net-(LED3-C2)") (class "Default")
      (node (ref "LED3") (pin "3") (pinfunction "C2_3") (pintype "bidirectional"))
      (node (ref "R5") (pin "2") (pinfunction "2_2") (pintype "passive"))
    )
    (net (code "26") (name "Net-(LED4-C1)") (class "Default")
      (node (ref "LED4") (pin "2") (pinfunction "C1_2") (pintype "bidirectional"))
      (node (ref "R8") (pin "1") (pinfunction "1_1") (pintype "passive"))
    )
    (net (code "27") (name "Net-(LED4-C2)") (class "Default")
      (node (ref "LED4") (pin "3") (pinfunction "C2_3") (pintype "bidirectional"))
      (node (ref "R7") (pin "2") (pinfunction "2_2") (pintype "passive"))
    )
    (net (code "28") (name "Net-(LED5-C1)") (class "Default")
      (node (ref "LED5") (pin "2") (pinfunction "C1_2") (pintype "bidirectional"))
      (node (ref "R36") (pin "1") (pinfunction "1_1") (pintype "passive"))
    )
    (net (code "29") (name "Net-(LED5-C2)") (class "Default")
      (node (ref "LED5") (pin "3") (pinfunction "C2_3") (pintype "bidirectional"))
      (node (ref "R37") (pin "2") (pinfunction "2_2") (pintype "passive"))
    )
    (net (code "30") (name "Net-(LED6-C1)") (class "Default")
      (node (ref "LED6") (pin "2") (pinfunction "C1_2") (pintype "bidirectional"))
      (node (ref "R33") (pin "1") (pinfunction "1_1") (pintype "passive"))
    )
    (net (code "31") (name "Net-(LED6-C2)") (class "Default")
      (node (ref "LED6") (pin "3") (pinfunction "C2_3") (pintype "bidirectional"))
      (node (ref "R34") (pin "2") (pinfunction "2_2") (pintype "passive"))
    )
    (net (code "32") (name "Net-(LED7-C1)") (class "Default")
      (node (ref "LED7") (pin "2") (pinfunction "C1_2") (pintype "bidirectional"))
      (node (ref "R31") (pin "1") (pinfunction "1_1") (pintype "passive"))
    )
    (net (code "33") (name "Net-(LED7-C2)") (class "Default")
      (node (ref "LED7") (pin "3") (pinfunction "C2_3") (pintype "bidirectional"))
      (node (ref "R32") (pin "2") (pinfunction "2_2") (pintype "passive"))
    )
    (net (code "34") (name "Net-(LED8-PadC)") (class "Default")
      (node (ref "LED8") (pin "C") (pinfunction "C_C") (pintype "passive"))
      (node (ref "R9") (pin "1") (pinfunction "1_1") (pintype "passive"))
    )
    (net (code "35") (name "Net-(LED9-PadC)") (class "Default")
      (node (ref "LED9") (pin "C") (pinfunction "C_C") (pintype "passive"))
      (node (ref "R10") (pin "1") (pinfunction "1_1") (pintype "passive"))
    )
    (net (code "36") (name "Net-(LED10-PadC)") (class "Default")
      (node (ref "LED10") (pin "C") (pinfunction "C_C") (pintype "passive"))
      (node (ref "R11") (pin "1") (pinfunction "1_1") (pintype "passive"))
    )
    (net (code "37") (name "Net-(LED11-PadC)") (class "Default")
      (node (ref "LED11") (pin "C") (pinfunction "C_C") (pintype "passive"))
      (node (ref "R12") (pin "1") (pinfunction "1_1") (pintype "passive"))
    )
    (net (code "38") (name "Net-(LED12-PadC)") (class "Default")
      (node (ref "LED12") (pin "C") (pinfunction "C_C") (pintype "passive"))
      (node (ref "R13") (pin "1") (pinfunction "1_1") (pintype "passive"))
    )
    (net (code "39") (name "Net-(LED13-PadC)") (class "Default")
      (node (ref "LED13") (pin "C") (pinfunction "C_C") (pintype "passive"))
      (node (ref "R20") (pin "1") (pinfunction "1_1") (pintype "passive"))
    )
    (net (code "40") (name "Net-(LED16-PadC)") (class "Default")
      (node (ref "LED16") (pin "C") (pinfunction "C_C") (pintype "passive"))
      (node (ref "R21") (pin "1") (pinfunction "1_1") (pintype "passive"))
    )
    (net (code "41") (name "Net-(LED17-PadC)") (class "Default")
      (node (ref "LED17") (pin "C") (pinfunction "C_C") (pintype "passive"))
      (node (ref "R29") (pin "1") (pinfunction "1_1") (pintype "passive"))
    )
    (net (code "42") (name "Net-(R17-Pad2)") (class "Default")
      (node (ref "R17") (pin "2") (pinfunction "2_2") (pintype "passive"))
      (node (ref "R18") (pin "2") (pinfunction "2_2") (pintype "passive"))
      (node (ref "SJ2") (pin "1") (pinfunction "1_1") (pintype "passive"))
    )
    (net (code "43") (name "Net-(TP1-1)") (class "Default")
      (node (ref "C29") (pin "1") (pinfunction "1_1") (pintype "passive"))
      (node (ref "R23") (pin "2") (pinfunction "2_2") (pintype "passive"))
      (node (ref "SJ1") (pin "2") (pinfunction "2_2") (pintype "passive"))
      (node (ref "TP1") (pin "P$1") (pinfunction "1_P$1") (pintype "bidirectional"))
      (node (ref "U3") (pin "43") (pinfunction "~{RESET}_43") (pintype "bidirectional"))
    )
    (net (code "44") (name "Net-(TP5-1)") (class "Default")
      (node (ref "LED14") (pin "A") (pinfunction "A_A") (pintype "passive"))
      (node (ref "R24") (pin "1") (pinfunction "1_1") (pintype "passive"))
      (node (ref "R26") (pin "2") (pinfunction "2_2") (pintype "passive"))
      (node (ref "R27") (pin "1") (pinfunction "1_1") (pintype "passive"))
      (node (ref "TP5") (pin "P$1") (pinfunction "1_P$1") (pintype "bidirectional"))
    )
    (net (code "45") (name "Net-(TP6-1)") (class "Default")
      (node (ref "R15") (pin "1") (pinfunction "1_1") (pintype "passive"))
      (node (ref "R16") (pin "2") (pinfunction "2_2") (pintype "passive"))
      (node (ref "TP6") (pin "P$1") (pinfunction "1_P$1") (pintype "bidirectional"))
      (node (ref "U3") (pin "13") (pinfunction "CFG_SEL2_13") (pintype "bidirectional"))
    )
    (net (code "46") (name "Net-(TP7-1)") (class "Default")
      (node (ref "TP7") (pin "P$1") (pinfunction "1_P$1") (pintype "bidirectional"))
      (node (ref "U1") (pin "2") (pinfunction "~{FLAGA}_2") (pintype "bidirectional"))
      (node (ref "U3") (pin "28") (pinfunction "~{OCS}_28") (pintype "bidirectional"))
    )
    (net (code "47") (name "Net-(TP8-1)") (class "Default")
      (node (ref "C7") (pin "+") (pinfunction "+_+") (pintype "passive"))
      (node (ref "J1") (pin "VBUS") (pinfunction "VBUS_VBUS") (pintype "bidirectional"))
      (node (ref "LED9") (pin "A") (pinfunction "A_A") (pintype "passive"))
      (node (ref "TP8") (pin "P$1") (pinfunction "1_P$1") (pintype "bidirectional"))
      (node (ref "U1") (pin "8") (pinfunction "OUTA_8") (pintype "bidirectional"))
    )
    (net (code "48") (name "Net-(TP9-1)") (class "Default")
      (node (ref "TP9") (pin "P$1") (pinfunction "1_P$1") (pintype "bidirectional"))
      (node (ref "U1") (pin "3") (pinfunction "~{FLAGB}_3") (pintype "bidirectional"))
      (node (ref "U3") (pin "27") (pinfunction "~{OCS}_27") (pintype "bidirectional"))
    )
    (net (code "49") (name "Net-(TP10-1)") (class "Default")
      (node (ref "C6") (pin "+") (pinfunction "+_+") (pintype "passive"))
      (node (ref "J2") (pin "VBUS") (pinfunction "VBUS_VBUS") (pintype "bidirectional"))
      (node (ref "LED11") (pin "A") (pinfunction "A_A") (pintype "passive"))
      (node (ref "TP10") (pin "P$1") (pinfunction "1_P$1") (pintype "bidirectional"))
      (node (ref "U1") (pin "5") (pinfunction "OUTB_5") (pintype "bidirectional"))
    )
    (net (code "50") (name "Net-(TP11-1)") (class "Default")
      (node (ref "TP11") (pin "P$1") (pinfunction "1_P$1") (pintype "bidirectional"))
      (node (ref "U2") (pin "2") (pinfunction "~{FLAGA}_2") (pintype "bidirectional"))
      (node (ref "U3") (pin "22") (pinfunction "~{OCS}_22") (pintype "bidirectional"))
    )
    (net (code "51") (name "Net-(TP12-1)") (class "Default")
      (node (ref "TP12") (pin "P$1") (pinfunction "1_P$1") (pintype "bidirectional"))
      (node (ref "U2") (pin "3") (pinfunction "~{FLAGB}_3") (pintype "bidirectional"))
      (node (ref "U3") (pin "21") (pinfunction "~{OCS}_21") (pintype "bidirectional"))
    )
    (net (code "52") (name "Net-(TP13-1)") (class "Default")
      (node (ref "C9") (pin "+") (pinfunction "+_+") (pintype "passive"))
      (node (ref "J3") (pin "VBUS") (pinfunction "VBUS_VBUS") (pintype "bidirectional"))
      (node (ref "LED10") (pin "A") (pinfunction "A_A") (pintype "passive"))
      (node (ref "TP13") (pin "P$1") (pinfunction "1_P$1") (pintype "bidirectional"))
      (node (ref "U2") (pin "8") (pinfunction "OUTA_8") (pintype "bidirectional"))
    )
    (net (code "53") (name "Net-(TP14-1)") (class "Default")
      (node (ref "C8") (pin "+") (pinfunction "+_+") (pintype "passive"))
      (node (ref "J4") (pin "VBUS") (pinfunction "VBUS_VBUS") (pintype "bidirectional"))
      (node (ref "LED12") (pin "A") (pinfunction "A_A") (pintype "passive"))
      (node (ref "TP14") (pin "P$1") (pinfunction "1_P$1") (pintype "bidirectional"))
      (node (ref "U2") (pin "5") (pinfunction "OUTB_5") (pintype "bidirectional"))
    )
    (net (code "54") (name "Net-(TP15-1)") (class "Default")
      (node (ref "TP15") (pin "P$1") (pinfunction "1_P$1") (pintype "bidirectional"))
      (node (ref "U3") (pin "35") (pinfunction "~{OCS}_35") (pintype "bidirectional"))
      (node (ref "U6") (pin "2") (pinfunction "~{FLAGA}_2") (pintype "bidirectional"))
    )
    (net (code "55") (name "Net-(TP16-1)") (class "Default")
      (node (ref "C32") (pin "+") (pinfunction "+_+") (pintype "passive"))
      (node (ref "J5") (pin "VBUS") (pinfunction "VBUS_VBUS") (pintype "bidirectional"))
      (node (ref "LED13") (pin "A") (pinfunction "A_A") (pintype "passive"))
      (node (ref "TP16") (pin "P$1") (pinfunction "1_P$1") (pintype "bidirectional"))
      (node (ref "U6") (pin "8") (pinfunction "OUTA_8") (pintype "bidirectional"))
    )
    (net (code "56") (name "Net-(TP17-1)") (class "Default")
      (node (ref "TP17") (pin "P$1") (pinfunction "1_P$1") (pintype "bidirectional"))
      (node (ref "U3") (pin "38") (pinfunction "~{OCS}_38") (pintype "bidirectional"))
      (node (ref "U7") (pin "2") (pinfunction "~{FLAGA}_2") (pintype "bidirectional"))
    )
    (net (code "57") (name "Net-(TP18-1)") (class "Default")
      (node (ref "TP18") (pin "P$1") (pinfunction "1_P$1") (pintype "bidirectional"))
      (node (ref "U3") (pin "37") (pinfunction "~{OCS}_37") (pintype "bidirectional"))
      (node (ref "U7") (pin "3") (pinfunction "~{FLAGB}_3") (pintype "bidirectional"))
    )
    (net (code "58") (name "Net-(TP19-1)") (class "Default")
      (node (ref "C35") (pin "+") (pinfunction "+_+") (pintype "passive"))
      (node (ref "J6") (pin "VBUS") (pinfunction "VBUS_VBUS") (pintype "bidirectional"))
      (node (ref "LED16") (pin "A") (pinfunction "A_A") (pintype "passive"))
      (node (ref "TP19") (pin "P$1") (pinfunction "1_P$1") (pintype "bidirectional"))
      (node (ref "U7") (pin "8") (pinfunction "OUTA_8") (pintype "bidirectional"))
    )
    (net (code "59") (name "Net-(TP20-1)") (class "Default")
      (node (ref "C30") (pin "+") (pinfunction "+_+") (pintype "passive"))
      (node (ref "J7") (pin "VBUS") (pinfunction "VBUS_VBUS") (pintype "bidirectional"))
      (node (ref "LED17") (pin "A") (pinfunction "A_A") (pintype "passive"))
      (node (ref "TP20") (pin "P$1") (pinfunction "1_P$1") (pintype "bidirectional"))
      (node (ref "U7") (pin "5") (pinfunction "OUTB_5") (pintype "bidirectional"))
    )
    (net (code "60") (name "Net-(U1-ENA)") (class "Default")
      (node (ref "R39") (pin "1") (pinfunction "1_1") (pintype "passive"))
      (node (ref "R40") (pin "1") (pinfunction "1_1") (pintype "passive"))
      (node (ref "U1") (pin "1") (pinfunction "ENA_1") (pintype "bidirectional"))
    )
    (net (code "61") (name "Net-(U1-ENB)") (class "Default")
      (node (ref "R41") (pin "2") (pinfunction "2_2") (pintype "passive"))
      (node (ref "R42") (pin "2") (pinfunction "2_2") (pintype "passive"))
      (node (ref "U1") (pin "4") (pinfunction "ENB_4") (pintype "bidirectional"))
    )
    (net (code "62") (name "Net-(U2-ENA)") (class "Default")
      (node (ref "R43") (pin "1") (pinfunction "1_1") (pintype "passive"))
      (node (ref "R44") (pin "1") (pinfunction "1_1") (pintype "passive"))
      (node (ref "U2") (pin "1") (pinfunction "ENA_1") (pintype "bidirectional"))
    )
    (net (code "63") (name "Net-(U2-ENB)") (class "Default")
      (node (ref "R45") (pin "2") (pinfunction "2_2") (pintype "passive"))
      (node (ref "R46") (pin "2") (pinfunction "2_2") (pintype "passive"))
      (node (ref "U2") (pin "4") (pinfunction "ENB_4") (pintype "bidirectional"))
    )
    (net (code "64") (name "Net-(U3A-CRFLT)") (class "Default")
      (node (ref "C20") (pin "1") (pinfunction "1_1") (pintype "passive"))
      (node (ref "C22") (pin "1") (pinfunction "1_1") (pintype "passive"))
      (node (ref "U3") (pin "25") (pinfunction "CRFLT_25") (pintype "bidirectional"))
    )
    (net (code "65") (name "Net-(U3A-LOC_PWR)") (class "Default")
      (node (ref "R22") (pin "2") (pinfunction "2_2") (pintype "passive"))
      (node (ref "U3") (pin "45") (pinfunction "LOC_PWR_45") (pintype "bidirectional"))
    )
    (net (code "66") (name "Net-(U3A-PLLFLT)") (class "Default")
      (node (ref "C17") (pin "1") (pinfunction "1_1") (pintype "passive"))
      (node (ref "C18") (pin "1") (pinfunction "1_1") (pintype "passive"))
      (node (ref "U3") (pin "62") (pinfunction "PLLFLT_62") (pintype "bidirectional"))
    )
    (net (code "67") (name "Net-(U3A-XIN)") (class "Default")
      (node (ref "C16") (pin "2") (pinfunction "2_2") (pintype "passive"))
      (node (ref "R19") (pin "1") (pinfunction "1_1") (pintype "passive"))
      (node (ref "U3") (pin "61") (pinfunction "XIN_61") (pintype "bidirectional"))
      (node (ref "Y1") (pin "P$2") (pinfunction "2_P$2") (pintype "passive"))
    )
    (net (code "68") (name "Net-(U3A-XOUT)") (class "Default")
      (node (ref "C15") (pin "1") (pinfunction "1_1") (pintype "passive"))
      (node (ref "R19") (pin "2") (pinfunction "2_2") (pintype "passive"))
      (node (ref "U3") (pin "60") (pinfunction "XOUT_60") (pintype "bidirectional"))
      (node (ref "Y1") (pin "P$1") (pinfunction "1_P$1") (pintype "passive"))
    )
    (net (code "69") (name "Net-(U3B-HS_IND{slash}CFG_CEL1)") (class "Default")
      (node (ref "R24") (pin "2") (pinfunction "2_2") (pintype "passive"))
      (node (ref "U3") (pin "42") (pinfunction "HS_IND/CFG_CEL1_42") (pintype "bidirectional"))
    )
    (net (code "70") (name "Net-(U3B-RBIAS)") (class "Default")
      (node (ref "R14") (pin "1") (pinfunction "1_1") (pintype "passive"))
      (node (ref "U3") (pin "63") (pinfunction "RBIAS_63") (pintype "bidirectional"))
    )
    (net (code "71") (name "Net-(U3B-VBUS_DET)") (class "Default")
      (node (ref "SJ2") (pin "2") (pinfunction "2_2") (pintype "passive"))
      (node (ref "U3") (pin "44") (pinfunction "VBUS_DET_44") (pintype "bidirectional"))
    )
    (net (code "72") (name "Net-(U3C-LEDA{slash}PRT_SWP)") (class "Default")
      (node (ref "R1") (pin "1") (pinfunction "1_1") (pintype "passive"))
      (node (ref "U3") (pin "51") (pinfunction "LEDA/PRT_SWP_51") (pintype "bidirectional"))
    )
    (net (code "73") (name "Net-(U3C-LEDB{slash}BOOST)") (class "Default")
      (node (ref "R2") (pin "2") (pinfunction "2_2") (pintype "passive"))
      (node (ref "U3") (pin "50") (pinfunction "LEDB/BOOST_50") (pintype "bidirectional"))
    )
    (net (code "74") (name "Net-(U3C-PRTPWR)") (class "Default")
      (node (ref "R40") (pin "2") (pinfunction "2_2") (pintype "passive"))
      (node (ref "U3") (pin "29") (pinfunction "PRTPWR_29") (pintype "bidirectional"))
    )
    (net (code "75") (name "Net-(U3C-USB_DN)") (class "Default")
      (node (ref "J1") (pin "D-") (pinfunction "D-_D-") (pintype "bidirectional"))
      (node (ref "U3") (pin "1") (pinfunction "USB_DN_1") (pintype "bidirectional"))
    )
    (net (code "76") (name "Net-(U3C-USB_DP)") (class "Default")
      (node (ref "J1") (pin "D+") (pinfunction "D+_D+") (pintype "bidirectional"))
      (node (ref "U3") (pin "2") (pinfunction "USB_DP_2") (pintype "bidirectional"))
    )
    (net (code "77") (name "Net-(U3D-LEDA{slash}PRT_SWP)") (class "Default")
      (node (ref "R3") (pin "1") (pinfunction "1_1") (pintype "passive"))
      (node (ref "U3") (pin "49") (pinfunction "LEDA/PRT_SWP_49") (pintype "bidirectional"))
    )
    (net (code "78") (name "Net-(U3D-LEDB{slash}BOOST)") (class "Default")
      (node (ref "R4") (pin "2") (pinfunction "2_2") (pintype "passive"))
      (node (ref "U3") (pin "48") (pinfunction "LEDB/BOOST_48") (pintype "bidirectional"))
    )
    (net (code "79") (name "Net-(U3D-PRTPWR)") (class "Default")
      (node (ref "R41") (pin "1") (pinfunction "1_1") (pintype "passive"))
      (node (ref "U3") (pin "26") (pinfunction "PRTPWR_26") (pintype "bidirectional"))
    )
    (net (code "80") (name "Net-(U3D-USB_DN)") (class "Default")
      (node (ref "J2") (pin "D-") (pinfunction "D-_D-") (pintype "bidirectional"))
      (node (ref "U3") (pin "3") (pinfunction "USB_DN_3") (pintype "bidirectional"))
    )
    (net (code "81") (name "Net-(U3D-USB_DP)") (class "Default")
      (node (ref "J2") (pin "D+") (pinfunction "D+_D+") (pintype "bidirectional"))
      (node (ref "U3") (pin "4") (pinfunction "USB_DP_4") (pintype "bidirectional"))
    )
    (net (code "82") (name "Net-(U3E-LEDA{slash}PRT_SWP)") (class "Default")
      (node (ref "R5") (pin "1") (pinfunction "1_1") (pintype "passive"))
      (node (ref "U3") (pin "47") (pinfunction "LEDA/PRT_SWP_47") (pintype "bidirectional"))
    )
    (net (code "83") (name "Net-(U3E-LEDB{slash}BOOST)") (class "Default")
      (node (ref "R6") (pin "2") (pinfunction "2_2") (pintype "passive"))
      (node (ref "U3") (pin "34") (pinfunction "LEDB/BOOST_34") (pintype "bidirectional"))
    )
    (net (code "84") (name "Net-(U3E-PRTPWR)") (class "Default")
      (node (ref "R43") (pin "2") (pinfunction "2_2") (pintype "passive"))
      (node (ref "U3") (pin "23") (pinfunction "PRTPWR_23") (pintype "bidirectional"))
    )
    (net (code "85") (name "Net-(U3E-USB_DN)") (class "Default")
      (node (ref "J3") (pin "D-") (pinfunction "D-_D-") (pintype "bidirectional"))
      (node (ref "U3") (pin "6") (pinfunction "USB_DN_6") (pintype "bidirectional"))
    )
    (net (code "86") (name "Net-(U3E-USB_DP)") (class "Default")
      (node (ref "J3") (pin "D+") (pinfunction "D+_D+") (pintype "bidirectional"))
      (node (ref "U3") (pin "7") (pinfunction "USB_DP_7") (pintype "bidirectional"))
    )
    (net (code "87") (name "Net-(U3F-LEDA{slash}PRT_SWP)") (class "Default")
      (node (ref "R7") (pin "1") (pinfunction "1_1") (pintype "passive"))
      (node (ref "U3") (pin "33") (pinfunction "LEDA/PRT_SWP_33") (pintype "bidirectional"))
    )
    (net (code "88") (name "Net-(U3F-LEDB{slash}BOOST)") (class "Default")
      (node (ref "R8") (pin "2") (pinfunction "2_2") (pintype "passive"))
      (node (ref "U3") (pin "32") (pinfunction "LEDB/BOOST_32") (pintype "bidirectional"))
    )
    (net (code "89") (name "Net-(U3F-PRTPWR)") (class "Default")
      (node (ref "R45") (pin "1") (pinfunction "1_1") (pintype "passive"))
      (node (ref "U3") (pin "20") (pinfunction "PRTPWR_20") (pintype "bidirectional"))
    )
    (net (code "90") (name "Net-(U3F-USB_DN)") (class "Default")
      (node (ref "J4") (pin "D-") (pinfunction "D-_D-") (pintype "bidirectional"))
      (node (ref "U3") (pin "8") (pinfunction "USB_DN_8") (pintype "bidirectional"))
    )
    (net (code "91") (name "Net-(U3F-USB_DP)") (class "Default")
      (node (ref "J4") (pin "D+") (pinfunction "D+_D+") (pintype "bidirectional"))
      (node (ref "U3") (pin "9") (pinfunction "USB_DP_9") (pintype "bidirectional"))
    )
    (net (code "92") (name "Net-(U3G-LEDA{slash}PRT_SWP)") (class "Default")
      (node (ref "R37") (pin "1") (pinfunction "1_1") (pintype "passive"))
      (node (ref "U3") (pin "31") (pinfunction "LEDA/PRT_SWP_31") (pintype "bidirectional"))
    )
    (net (code "93") (name "Net-(U3G-LEDB{slash}BOOST)") (class "Default")
      (node (ref "R36") (pin "2") (pinfunction "2_2") (pintype "passive"))
      (node (ref "U3") (pin "18") (pinfunction "LEDB/BOOST_18") (pintype "bidirectional"))
    )
    (net (code "94") (name "Net-(U3G-PRTPWR)") (class "Default")
      (node (ref "R47") (pin "2") (pinfunction "2_2") (pintype "passive"))
      (node (ref "U3") (pin "30") (pinfunction "PRTPWR_30") (pintype "bidirectional"))
    )
    (net (code "95") (name "Net-(U3G-USB_DN)") (class "Default")
      (node (ref "J5") (pin "D-") (pinfunction "D-_D-") (pintype "bidirectional"))
      (node (ref "U3") (pin "11") (pinfunction "USB_DN_11") (pintype "bidirectional"))
    )
    (net (code "96") (name "Net-(U3G-USB_DP)") (class "Default")
      (node (ref "J5") (pin "D+") (pinfunction "D+_D+") (pintype "bidirectional"))
      (node (ref "U3") (pin "12") (pinfunction "USB_DP_12") (pintype "bidirectional"))
    )
    (net (code "97") (name "Net-(U3H-LEDA{slash}PRT_SWP)") (class "Default")
      (node (ref "R34") (pin "1") (pinfunction "1_1") (pintype "passive"))
      (node (ref "U3") (pin "17") (pinfunction "LEDA/PRT_SWP_17") (pintype "bidirectional"))
    )
    (net (code "98") (name "Net-(U3H-LEDB{slash}BOOST)") (class "Default")
      (node (ref "R33") (pin "2") (pinfunction "2_2") (pintype "passive"))
      (node (ref "U3") (pin "16") (pinfunction "LEDB/BOOST_16") (pintype "bidirectional"))
    )
    (net (code "99") (name "Net-(U3H-PRTPWR)") (class "Default")
      (node (ref "R49") (pin "2") (pinfunction "2_2") (pintype "passive"))
      (node (ref "U3") (pin "39") (pinfunction "PRTPWR_39") (pintype "bidirectional"))
    )
    (net (code "100") (name "Net-(U3H-USB_DN)") (class "Default")
      (node (ref "J6") (pin "D-") (pinfunction "D-_D-") (pintype "bidirectional"))
      (node (ref "U3") (pin "53") (pinfunction "USB_DN_53") (pintype "bidirectional"))
    )
    (net (code "101") (name "Net-(U3H-USB_DP)") (class "Default")
      (node (ref "J6") (pin "D+") (pinfunction "D+_D+") (pintype "bidirectional"))
      (node (ref "U3") (pin "54") (pinfunction "USB_DP_54") (pintype "bidirectional"))
    )
    (net (code "102") (name "Net-(U3I-LEDA{slash}PRT_SWP)") (class "Default")
      (node (ref "R32") (pin "1") (pinfunction "1_1") (pintype "passive"))
      (node (ref "U3") (pin "15") (pinfunction "LEDA/PRT_SWP_15") (pintype "bidirectional"))
    )
    (net (code "103") (name "Net-(U3I-LEDB{slash}BOOST)") (class "Default")
      (node (ref "R31") (pin "2") (pinfunction "2_2") (pintype "passive"))
      (node (ref "U3") (pin "14") (pinfunction "LEDB/BOOST_14") (pintype "bidirectional"))
    )
    (net (code "104") (name "Net-(U3I-PRTPWR)") (class "Default")
      (node (ref "R51") (pin "1") (pinfunction "1_1") (pintype "passive"))
      (node (ref "U3") (pin "36") (pinfunction "PRTPWR_36") (pintype "bidirectional"))
    )
    (net (code "105") (name "Net-(U3I-USB_DN)") (class "Default")
      (node (ref "J7") (pin "D-") (pinfunction "D-_D-") (pintype "bidirectional"))
      (node (ref "U3") (pin "55") (pinfunction "USB_DN_55") (pintype "bidirectional"))
    )
    (net (code "106") (name "Net-(U3I-USB_DP)") (class "Default")
      (node (ref "J7") (pin "D+") (pinfunction "D+_D+") (pintype "bidirectional"))
      (node (ref "U3") (pin "56") (pinfunction "USB_DP_56") (pintype "bidirectional"))
    )
    (net (code "107") (name "Net-(U6-ENA)") (class "Default")
      (node (ref "R47") (pin "1") (pinfunction "1_1") (pintype "passive"))
      (node (ref "R48") (pin "1") (pinfunction "1_1") (pintype "passive"))
      (node (ref "U6") (pin "1") (pinfunction "ENA_1") (pintype "bidirectional"))
    )
    (net (code "108") (name "Net-(U6-ENB)") (class "Default")
      (node (ref "R30") (pin "2") (pinfunction "2_2") (pintype "passive"))
      (node (ref "U6") (pin "4") (pinfunction "ENB_4") (pintype "bidirectional"))
    )
    (net (code "109") (name "Net-(U7-ENA)") (class "Default")
      (node (ref "R49") (pin "1") (pinfunction "1_1") (pintype "passive"))
      (node (ref "R50") (pin "1") (pinfunction "1_1") (pintype "passive"))
      (node (ref "U7") (pin "1") (pinfunction "ENA_1") (pintype "bidirectional"))
    )
    (net (code "110") (name "Net-(U7-ENB)") (class "Default")
      (node (ref "R51") (pin "2") (pinfunction "2_2") (pintype "passive"))
      (node (ref "R52") (pin "2") (pinfunction "2_2") (pintype "passive"))
      (node (ref "U7") (pin "4") (pinfunction "ENB_4") (pintype "bidirectional"))
    )
    (net (code "111") (name "PE") (class "Default")
      (node (ref "C28") (pin "1") (pinfunction "1_1") (pintype "passive"))
      (node (ref "J0") (pin "S1") (pinfunction "P$1_S1") (pintype "bidirectional"))
      (node (ref "J0") (pin "S2") (pinfunction "P$2_S2") (pintype "bidirectional"))
      (node (ref "J1") (pin "S1") (pinfunction "P$1_S1") (pintype "bidirectional"))
      (node (ref "J1") (pin "S2") (pinfunction "P$2_S2") (pintype "bidirectional"))
      (node (ref "J2") (pin "S1") (pinfunction "P$1_S1") (pintype "bidirectional"))
      (node (ref "J2") (pin "S2") (pinfunction "P$2_S2") (pintype "bidirectional"))
      (node (ref "J3") (pin "S1") (pinfunction "P$1_S1") (pintype "bidirectional"))
      (node (ref "J3") (pin "S2") (pinfunction "P$2_S2") (pintype "bidirectional"))
      (node (ref "J4") (pin "S1") (pinfunction "P$1_S1") (pintype "bidirectional"))
      (node (ref "J4") (pin "S2") (pinfunction "P$2_S2") (pintype "bidirectional"))
      (node (ref "J5") (pin "S1") (pinfunction "P$1_S1") (pintype "bidirectional"))
      (node (ref "J5") (pin "S2") (pinfunction "P$2_S2") (pintype "bidirectional"))
      (node (ref "J6") (pin "S1") (pinfunction "P$1_S1") (pintype "bidirectional"))
      (node (ref "J6") (pin "S2") (pinfunction "P$2_S2") (pintype "bidirectional"))
      (node (ref "J7") (pin "S1") (pinfunction "P$1_S1") (pintype "bidirectional"))
      (node (ref "J7") (pin "S2") (pinfunction "P$2_S2") (pintype "bidirectional"))
      (node (ref "R38") (pin "1") (pinfunction "1_1") (pintype "passive"))
    )
    (net (code "112") (name "unconnected-(IC1-EN-Pad7)") (class "Default")
      (node (ref "IC1") (pin "7") (pinfunction "EN_7") (pintype "bidirectional"))
    )
    (net (code "113") (name "unconnected-(J8-SWITCH-Pad5)") (class "Default")
      (node (ref "J8") (pin "5") (pinfunction "SWITCH_5") (pintype "bidirectional"))
    )
    (net (code "114") (name "unconnected-(J9-SWITCH-Pad5)") (class "Default")
      (node (ref "J9") (pin "5") (pinfunction "SWITCH_5") (pintype "bidirectional"))
    )
    (net (code "115") (name "unconnected-(U6-OUTB-Pad5)") (class "Default")
      (node (ref "U6") (pin "5") (pinfunction "OUTB_5") (pintype "bidirectional"))
    )
    (net (code "116") (name "unconnected-(U6-~{FLAGB}-Pad3)") (class "Default")
      (node (ref "U6") (pin "3") (pinfunction "~{FLAGB}_3") (pintype "bidirectional"))
    )
  )
)
